# Shift_register_map.net
KiCad netlist of a schematic drawn in Altium Designer
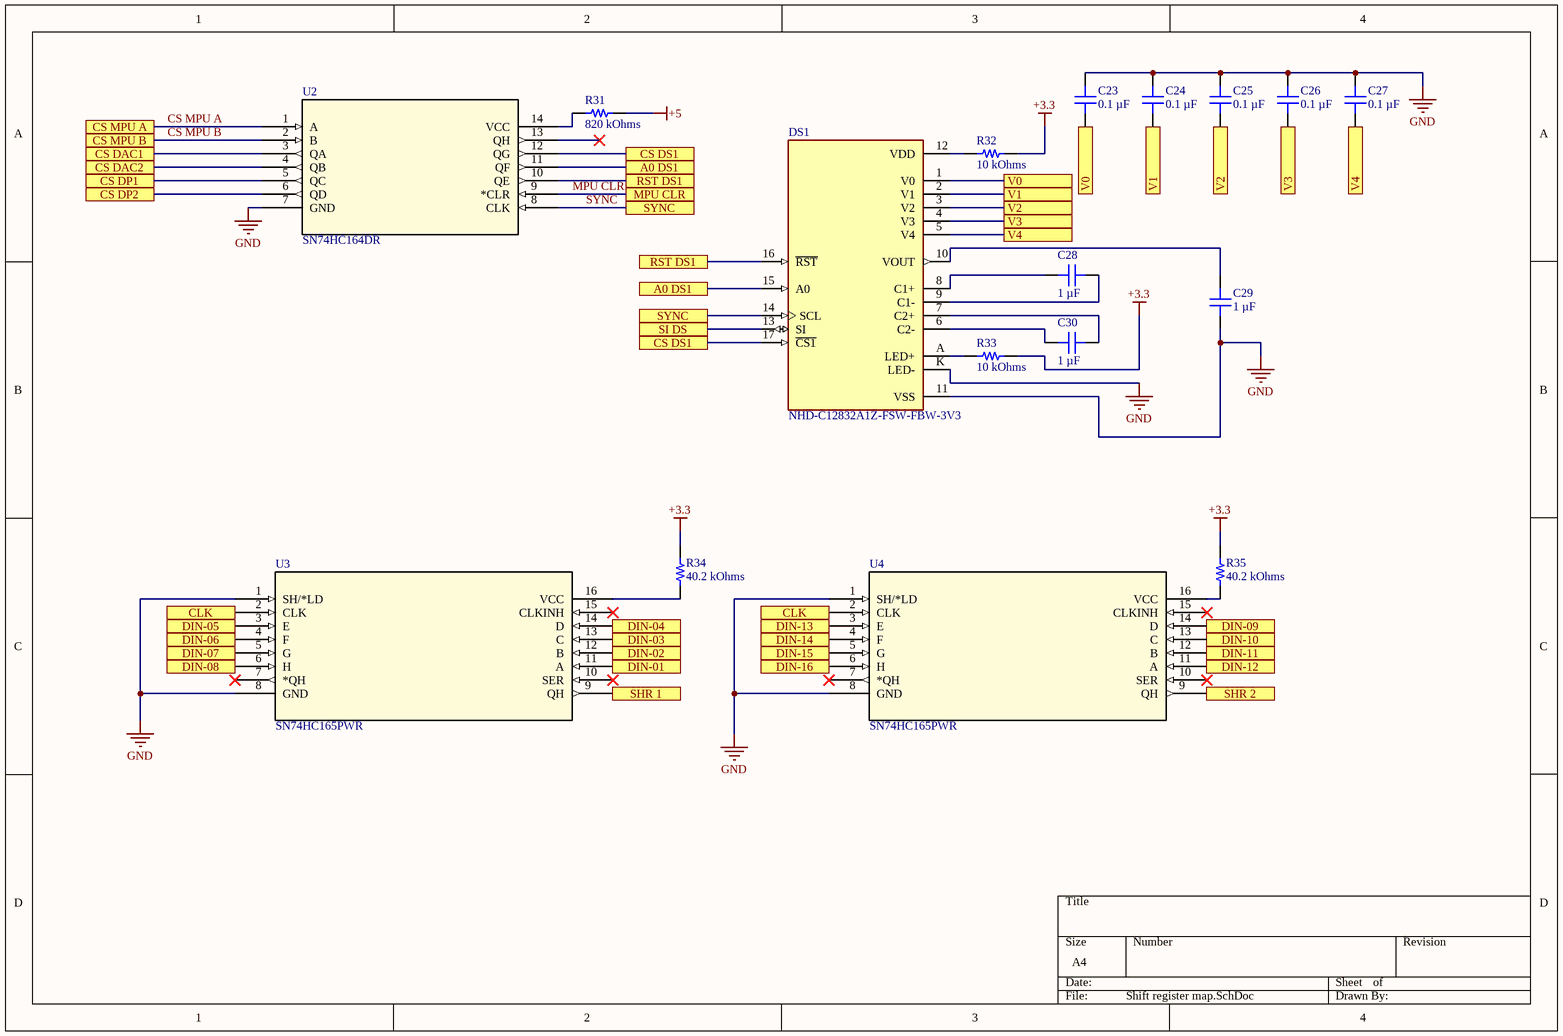
[diagram p0: Shift register map.SchDoc]

(export (version "E")
  (design (tool "Eeschema 10.0.6"))
  (components
    (comp (ref "C23")
      (value "0.1 µF")
      (footprint "CAP 1210_3225 - 1MM")
      (description "CAP1210 X7R .1UF 10% 100V")
      (fields
        (field (name "PART NUMBER") "GMC32X7R104K100NT")
        (field (name "MANUFACTURER") "Cal-Chip Electronics, Inc.")
      )
      (libsource (lib "Celestial Altium Library - altium_library(1)") (part "Capacitor"))
    )
    (comp (ref "C24")
      (value "0.1 µF")
      (footprint "CAP 1210_3225 - 1MM")
      (description "CAP1210 X7R .1UF 10% 100V")
      (fields
        (field (name "PART NUMBER") "GMC32X7R104K100NT")
        (field (name "MANUFACTURER") "Cal-Chip Electronics, Inc.")
      )
      (libsource (lib "Celestial Altium Library - altium_library(1)") (part "Capacitor"))
    )
    (comp (ref "C25")
      (value "0.1 µF")
      (footprint "CAP 1210_3225 - 1MM")
      (description "CAP1210 X7R .1UF 10% 100V")
      (fields
        (field (name "PART NUMBER") "GMC32X7R104K100NT")
        (field (name "MANUFACTURER") "Cal-Chip Electronics, Inc.")
      )
      (libsource (lib "Celestial Altium Library - altium_library(1)") (part "Capacitor"))
    )
    (comp (ref "C26")
      (value "0.1 µF")
      (footprint "CAP 1210_3225 - 1MM")
      (description "CAP1210 X7R .1UF 10% 100V")
      (fields
        (field (name "PART NUMBER") "GMC32X7R104K100NT")
        (field (name "MANUFACTURER") "Cal-Chip Electronics, Inc.")
      )
      (libsource (lib "Celestial Altium Library - altium_library(1)") (part "Capacitor"))
    )
    (comp (ref "C27")
      (value "0.1 µF")
      (footprint "CAP 1210_3225 - 1MM")
      (description "CAP1210 X7R .1UF 10% 100V")
      (fields
        (field (name "PART NUMBER") "GMC32X7R104K100NT")
        (field (name "MANUFACTURER") "Cal-Chip Electronics, Inc.")
      )
      (libsource (lib "Celestial Altium Library - altium_library(1)") (part "Capacitor"))
    )
    (comp (ref "C28")
      (value "1 µF")
      (footprint "CAP 1210_3225 - 1MM")
      (description "CAP1210 X7R 1UF 10% 25V")
      (fields
        (field (name "PART NUMBER") "GMC32X7R105K25NT")
        (field (name "MANUFACTURER") "Cal-Chip Electronics, Inc.")
      )
      (libsource (lib "Celestial Altium Library - altium_library(1)") (part "Capacitor"))
    )
    (comp (ref "C29")
      (value "1 µF")
      (footprint "CAP 1210_3225 - 1MM")
      (description "CAP1210 X7R 1UF 10% 25V")
      (fields
        (field (name "PART NUMBER") "GMC32X7R105K25NT")
        (field (name "MANUFACTURER") "Cal-Chip Electronics, Inc.")
      )
      (libsource (lib "Celestial Altium Library - altium_library(1)") (part "Capacitor"))
    )
    (comp (ref "C30")
      (value "1 µF")
      (footprint "CAP 1210_3225 - 1MM")
      (description "CAP1210 X7R 1UF 10% 25V")
      (fields
        (field (name "PART NUMBER") "GMC32X7R105K25NT")
        (field (name "MANUFACTURER") "Cal-Chip Electronics, Inc.")
      )
      (libsource (lib "Celestial Altium Library - altium_library(1)") (part "Capacitor"))
    )
    (comp (ref "DS1")
      (value "NHD-C12832A1Z-FSW-FBW-3V3")
      (footprint "LCD_NHD-C12832A1Z-FSW-FBW-3V3")
      (fields (field (name "MF") "Newhaven"))
      (libsource (lib "NHD-C12832A1Z-FSW-FBW-3V3") (part "NHD-C12832A1Z-FSW-FBW-3V3"))
    )
    (comp (ref "R31")
      (value "820 kOhms")
      (footprint "RES 1210_3225")
      (description "RES 820K OHM 5% 1/3W 1210")
      (fields
        (field (name "PART NUMBER") "RMCF1210JT820K")
        (field (name "MANUFACTURER") "Stackpole Electronics Inc")
      )
      (libsource (lib "Celestial Altium Library - altium_library(1)") (part "Resistor"))
    )
    (comp (ref "R32")
      (value "10 kOhms")
      (footprint "RES 1210_3225")
      (description "RES 10K OHM 0.1% 1/2W 1210")
      (fields (field (name "PART NUMBER") "TNPW121010K0BEEN") (field (name "MANUFACTURER") "Vishay Dale"))
      (libsource (lib "Celestial Altium Library - altium_library(1)") (part "Resistor"))
    )
    (comp (ref "R33")
      (value "10 kOhms")
      (footprint "RES 1210_3225")
      (description "RES 10K OHM 0.1% 1/2W 1210")
      (fields (field (name "PART NUMBER") "TNPW121010K0BEEN") (field (name "MANUFACTURER") "Vishay Dale"))
      (libsource (lib "Celestial Altium Library - altium_library(1)") (part "Resistor"))
    )
    (comp (ref "R34")
      (value "40.2 kOhms")
      (footprint "RES 1206_3216")
      (description "RES 40.2K OHM 1% 1/4W 1206")
      (fields
        (field (name "PART NUMBER") "RMCF1206FT40K2")
        (field (name "MANUFACTURER") "Stackpole Electronics Inc")
      )
      (libsource (lib "Celestial Altium Library - altium_library(1)") (part "Resistor"))
    )
    (comp (ref "R35")
      (value "40.2 kOhms")
      (footprint "RES 1206_3216")
      (description "RES 40.2K OHM 1% 1/4W 1206")
      (fields
        (field (name "PART NUMBER") "RMCF1206FT40K2")
        (field (name "MANUFACTURER") "Stackpole Electronics Inc")
      )
      (libsource (lib "Celestial Altium Library - altium_library(1)") (part "Resistor"))
    )
    (comp (ref "U2")
      (value "SN74HC164DR")
      (footprint "SOP14")
      (description "No Description Available")
      (libsource (lib "SN74HC164DR") (part "SN74HC164DR"))
    )
    (comp (ref "U3")
      (value "SN74HC165PWR")
      (footprint "PW16")
      (description "No Description Available")
      (libsource (lib "SN74HC165PWR") (part "SN74HC165PWR"))
    )
    (comp (ref "U4")
      (value "SN74HC165PWR")
      (footprint "PW16")
      (description "No Description Available")
      (libsource (lib "SN74HC165PWR") (part "SN74HC165PWR"))
    )
  )
  (nets
    (net (code "1") (name "+3.3") (class "Default")
      (node (ref "R32") (pin "2") (pinfunction "2_2") (pintype "passive"))
      (node (ref "R33") (pin "2") (pinfunction "2_2") (pintype "passive"))
      (node (ref "R34") (pin "2") (pinfunction "2_2") (pintype "passive"))
      (node (ref "R35") (pin "2") (pinfunction "2_2") (pintype "passive"))
    )
    (net (code "2") (name "+5") (class "Default")
      (node (ref "R31") (pin "2") (pinfunction "2_2") (pintype "passive"))
    )
    (net (code "3") (name "/A0 DS1") (class "Default")
      (node (ref "DS1") (pin "15") (pinfunction "A0_15") (pintype "input"))
      (node (ref "U2") (pin "11") (pinfunction "QF_11") (pintype "output"))
    )
    (net (code "4") (name "/CLK") (class "Default")
      (node (ref "U3") (pin "2") (pinfunction "CLK_2") (pintype "input"))
      (node (ref "U4") (pin "2") (pinfunction "CLK_2") (pintype "input"))
    )
    (net (code "5") (name "/CS DAC1") (class "Default")
      (node (ref "U2") (pin "3") (pinfunction "QA_3") (pintype "output"))
    )
    (net (code "6") (name "/CS DAC2") (class "Default")
      (node (ref "U2") (pin "4") (pinfunction "QB_4") (pintype "output"))
    )
    (net (code "7") (name "/CS DP1") (class "Default")
      (node (ref "U2") (pin "5") (pinfunction "QC_5") (pintype "output"))
    )
    (net (code "8") (name "/CS DP2") (class "Default")
      (node (ref "U2") (pin "6") (pinfunction "QD_6") (pintype "output"))
    )
    (net (code "9") (name "/CS DS1") (class "Default")
      (node (ref "DS1") (pin "17") (pinfunction "~{CS1}_17") (pintype "input"))
      (node (ref "U2") (pin "12") (pinfunction "QG_12") (pintype "output"))
    )
    (net (code "10") (name "/CS MPU A") (class "Default")
      (node (ref "U2") (pin "1") (pinfunction "A_1") (pintype "input"))
    )
    (net (code "11") (name "/CS MPU B") (class "Default")
      (node (ref "U2") (pin "2") (pinfunction "B_2") (pintype "input"))
    )
    (net (code "12") (name "/DIN-01") (class "Default")
      (node (ref "U3") (pin "11") (pinfunction "A_11") (pintype "input"))
    )
    (net (code "13") (name "/DIN-02") (class "Default")
      (node (ref "U3") (pin "12") (pinfunction "B_12") (pintype "input"))
    )
    (net (code "14") (name "/DIN-03") (class "Default")
      (node (ref "U3") (pin "13") (pinfunction "C_13") (pintype "input"))
    )
    (net (code "15") (name "/DIN-04") (class "Default")
      (node (ref "U3") (pin "14") (pinfunction "D_14") (pintype "input"))
    )
    (net (code "16") (name "/DIN-05") (class "Default")
      (node (ref "U3") (pin "3") (pinfunction "E_3") (pintype "input"))
    )
    (net (code "17") (name "/DIN-06") (class "Default")
      (node (ref "U3") (pin "4") (pinfunction "F_4") (pintype "input"))
    )
    (net (code "18") (name "/DIN-07") (class "Default")
      (node (ref "U3") (pin "5") (pinfunction "G_5") (pintype "input"))
    )
    (net (code "19") (name "/DIN-08") (class "Default")
      (node (ref "U3") (pin "6") (pinfunction "H_6") (pintype "input"))
    )
    (net (code "20") (name "/DIN-09") (class "Default")
      (node (ref "U4") (pin "14") (pinfunction "D_14") (pintype "input"))
    )
    (net (code "21") (name "/DIN-10") (class "Default")
      (node (ref "U4") (pin "13") (pinfunction "C_13") (pintype "input"))
    )
    (net (code "22") (name "/DIN-11") (class "Default")
      (node (ref "U4") (pin "12") (pinfunction "B_12") (pintype "input"))
    )
    (net (code "23") (name "/DIN-12") (class "Default")
      (node (ref "U4") (pin "11") (pinfunction "A_11") (pintype "input"))
    )
    (net (code "24") (name "/DIN-13") (class "Default")
      (node (ref "U4") (pin "3") (pinfunction "E_3") (pintype "input"))
    )
    (net (code "25") (name "/DIN-14") (class "Default")
      (node (ref "U4") (pin "4") (pinfunction "F_4") (pintype "input"))
    )
    (net (code "26") (name "/DIN-15") (class "Default")
      (node (ref "U4") (pin "5") (pinfunction "G_5") (pintype "input"))
    )
    (net (code "27") (name "/DIN-16") (class "Default")
      (node (ref "U4") (pin "6") (pinfunction "H_6") (pintype "input"))
    )
    (net (code "28") (name "/MPU CLR") (class "Default")
      (node (ref "U2") (pin "9") (pinfunction "*CLR_9") (pintype "input"))
    )
    (net (code "29") (name "/RST DS1") (class "Default")
      (node (ref "DS1") (pin "16") (pinfunction "~{RST}_16") (pintype "input"))
      (node (ref "U2") (pin "10") (pinfunction "QE_10") (pintype "output"))
    )
    (net (code "30") (name "/SHR 1") (class "Default")
      (node (ref "U3") (pin "9") (pinfunction "QH_9") (pintype "output"))
    )
    (net (code "31") (name "/SHR 2") (class "Default")
      (node (ref "U4") (pin "9") (pinfunction "QH_9") (pintype "output"))
    )
    (net (code "32") (name "/SI DS") (class "Default")
      (node (ref "DS1") (pin "13") (pinfunction "SI_13") (pintype "bidirectional"))
    )
    (net (code "33") (name "/SYNC") (class "Default")
      (node (ref "DS1") (pin "14") (pinfunction "SCL_14") (pintype "input"))
      (node (ref "U2") (pin "8") (pinfunction "CLK_8") (pintype "input"))
    )
    (net (code "34") (name "/V0") (class "Default")
      (node (ref "C23") (pin "1") (pinfunction "1_1") (pintype "passive"))
      (node (ref "DS1") (pin "1") (pinfunction "V0_1") (pintype "power_in"))
    )
    (net (code "35") (name "/V1") (class "Default")
      (node (ref "C24") (pin "1") (pinfunction "1_1") (pintype "passive"))
      (node (ref "DS1") (pin "2") (pinfunction "V1_2") (pintype "power_in"))
    )
    (net (code "36") (name "/V2") (class "Default")
      (node (ref "C25") (pin "1") (pinfunction "1_1") (pintype "passive"))
      (node (ref "DS1") (pin "3") (pinfunction "V2_3") (pintype "power_in"))
    )
    (net (code "37") (name "/V3") (class "Default")
      (node (ref "C26") (pin "1") (pinfunction "1_1") (pintype "passive"))
      (node (ref "DS1") (pin "4") (pinfunction "V3_4") (pintype "power_in"))
    )
    (net (code "38") (name "/V4") (class "Default")
      (node (ref "C27") (pin "1") (pinfunction "1_1") (pintype "passive"))
      (node (ref "DS1") (pin "5") (pinfunction "V4_5") (pintype "power_in"))
    )
    (net (code "39") (name "GND") (class "Default")
      (node (ref "C23") (pin "2") (pinfunction "2_2") (pintype "passive"))
      (node (ref "C24") (pin "2") (pinfunction "2_2") (pintype "passive"))
      (node (ref "C25") (pin "2") (pinfunction "2_2") (pintype "passive"))
      (node (ref "C26") (pin "2") (pinfunction "2_2") (pintype "passive"))
      (node (ref "C27") (pin "2") (pinfunction "2_2") (pintype "passive"))
      (node (ref "C29") (pin "1") (pinfunction "1_1") (pintype "passive"))
      (node (ref "DS1") (pin "11") (pinfunction "VSS_11") (pintype "power_in"))
      (node (ref "DS1") (pin "K") (pinfunction "LED-_K") (pintype "passive"))
      (node (ref "U2") (pin "7") (pinfunction "GND_7") (pintype "power_in"))
      (node (ref "U3") (pin "1") (pinfunction "SH/*LD_1") (pintype "input"))
      (node (ref "U3") (pin "8") (pinfunction "GND_8") (pintype "power_in"))
      (node (ref "U4") (pin "1") (pinfunction "SH/*LD_1") (pintype "input"))
      (node (ref "U4") (pin "8") (pinfunction "GND_8") (pintype "power_in"))
    )
    (net (code "40") (name "Net-(DS1-C1+)") (class "Default")
      (node (ref "C28") (pin "1") (pinfunction "1_1") (pintype "passive"))
      (node (ref "DS1") (pin "8") (pinfunction "C1+_8") (pintype "passive"))
    )
    (net (code "41") (name "Net-(DS1-C1-)") (class "Default")
      (node (ref "C28") (pin "2") (pinfunction "2_2") (pintype "passive"))
      (node (ref "DS1") (pin "9") (pinfunction "C1-_9") (pintype "passive"))
    )
    (net (code "42") (name "Net-(DS1-C2+)") (class "Default")
      (node (ref "C30") (pin "2") (pinfunction "2_2") (pintype "passive"))
      (node (ref "DS1") (pin "7") (pinfunction "C2+_7") (pintype "passive"))
    )
    (net (code "43") (name "Net-(DS1-C2-)") (class "Default")
      (node (ref "C30") (pin "1") (pinfunction "1_1") (pintype "passive"))
      (node (ref "DS1") (pin "6") (pinfunction "C2-_6") (pintype "passive"))
    )
    (net (code "44") (name "Net-(DS1-LED+)") (class "Default")
      (node (ref "DS1") (pin "A") (pinfunction "LED+_A") (pintype "passive"))
      (node (ref "R33") (pin "1") (pinfunction "1_1") (pintype "passive"))
    )
    (net (code "45") (name "Net-(DS1-VDD)") (class "Default")
      (node (ref "DS1") (pin "12") (pinfunction "VDD_12") (pintype "power_in"))
      (node (ref "R32") (pin "1") (pinfunction "1_1") (pintype "passive"))
    )
    (net (code "46") (name "Net-(DS1-VOUT)") (class "Default")
      (node (ref "C29") (pin "2") (pinfunction "2_2") (pintype "passive"))
      (node (ref "DS1") (pin "10") (pinfunction "VOUT_10") (pintype "output"))
    )
    (net (code "47") (name "Net-(U2-VCC)") (class "Default")
      (node (ref "R31") (pin "1") (pinfunction "1_1") (pintype "passive"))
      (node (ref "U2") (pin "14") (pinfunction "VCC_14") (pintype "power_in"))
    )
    (net (code "48") (name "Net-(U3-VCC)") (class "Default")
      (node (ref "R34") (pin "1") (pinfunction "1_1") (pintype "passive"))
      (node (ref "U3") (pin "16") (pinfunction "VCC_16") (pintype "power_in"))
    )
    (net (code "49") (name "Net-(U4-VCC)") (class "Default")
      (node (ref "R35") (pin "1") (pinfunction "1_1") (pintype "passive"))
      (node (ref "U4") (pin "16") (pinfunction "VCC_16") (pintype "power_in"))
    )
    (net (code "50") (name "unconnected-(U2-QH-Pad13)") (class "Default")
      (node (ref "U2") (pin "13") (pinfunction "QH_13") (pintype "output+no_connect"))
    )
    (net (code "51") (name "unconnected-(U3-*QH-Pad7)") (class "Default")
      (node (ref "U3") (pin "7") (pinfunction "*QH_7") (pintype "output+no_connect"))
    )
    (net (code "52") (name "unconnected-(U3-CLKINH-Pad15)") (class "Default")
      (node (ref "U3") (pin "15") (pinfunction "CLKINH_15") (pintype "input+no_connect"))
    )
    (net (code "53") (name "unconnected-(U3-SER-Pad10)") (class "Default")
      (node (ref "U3") (pin "10") (pinfunction "SER_10") (pintype "input+no_connect"))
    )
    (net (code "54") (name "unconnected-(U4-*QH-Pad7)") (class "Default")
      (node (ref "U4") (pin "7") (pinfunction "*QH_7") (pintype "output+no_connect"))
    )
    (net (code "55") (name "unconnected-(U4-CLKINH-Pad15)") (class "Default")
      (node (ref "U4") (pin "15") (pinfunction "CLKINH_15") (pintype "input+no_connect"))
    )
    (net (code "56") (name "unconnected-(U4-SER-Pad10)") (class "Default")
      (node (ref "U4") (pin "10") (pinfunction "SER_10") (pintype "input+no_connect"))
    )
  )
)
